# Arduino_EPROM_Reader.net
KiCad netlist of a schematic drawn in EAGLE
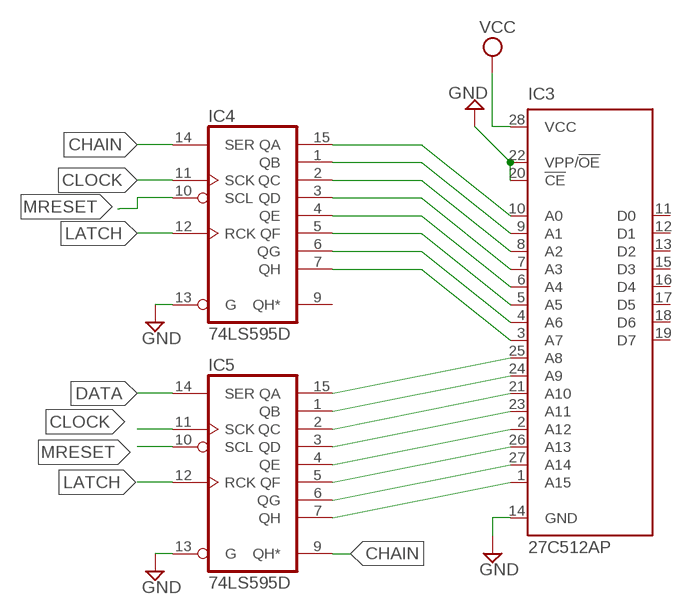
[diagram p0: schematic, sheet 1]

(export (version "E")
  (design (tool "Eeschema 10.0.6"))
  (components
    (comp (ref "IC3")
      (value "27C512AP")
      (footprint "eagle-import:DIL28-6")
      (fields (field (name "MPN") "M27C512-90B6"))
      (libsource (lib "eagle-import") (part "27512APC"))
    )
    (comp (ref "IC4")
      (value "74LS595D")
      (footprint "eagle-import:SO16")
      (libsource (lib "eagle-import") (part "74595DLS"))
    )
    (comp (ref "IC5")
      (value "74LS595D")
      (footprint "eagle-import:SO16")
      (libsource (lib "eagle-import") (part "74595DLS"))
    )
  )
  (nets
    (net (code "1") (name "CHAIN") (class "Default")
      (node (ref "IC4") (pin "14") (pinfunction "SER_14") (pintype "input"))
      (node (ref "IC5") (pin "9") (pinfunction "QH*_9") (pintype "tri_state"))
    )
    (net (code "2") (name "CLOCK") (class "Default")
      (node (ref "IC4") (pin "11") (pinfunction "SCK_11") (pintype "input"))
      (node (ref "IC5") (pin "11") (pinfunction "SCK_11") (pintype "input"))
    )
    (net (code "3") (name "DATA") (class "Default")
      (node (ref "IC5") (pin "14") (pinfunction "SER_14") (pintype "input"))
    )
    (net (code "4") (name "GND") (class "Default")
      (node (ref "IC3") (pin "14") (pinfunction "GND_14") (pintype "power_in"))
      (node (ref "IC3") (pin "20") (pinfunction "~{CE}_20") (pintype "input"))
      (node (ref "IC3") (pin "22") (pinfunction "VPP/~{OE}_22") (pintype "input"))
      (node (ref "IC4") (pin "13") (pinfunction "G_13") (pintype "input"))
      (node (ref "IC5") (pin "13") (pinfunction "G_13") (pintype "input"))
    )
    (net (code "5") (name "LATCH") (class "Default")
      (node (ref "IC4") (pin "12") (pinfunction "RCK_12") (pintype "input"))
      (node (ref "IC5") (pin "12") (pinfunction "RCK_12") (pintype "input"))
    )
    (net (code "6") (name "MRESET") (class "Default")
      (node (ref "IC4") (pin "10") (pinfunction "SCL_10") (pintype "input"))
      (node (ref "IC5") (pin "10") (pinfunction "SCL_10") (pintype "input"))
    )
    (net (code "7") (name "Net-(IC3-A0)") (class "Default")
      (node (ref "IC3") (pin "10") (pinfunction "A0_10") (pintype "input"))
      (node (ref "IC4") (pin "15") (pinfunction "QA_15") (pintype "tri_state"))
    )
    (net (code "8") (name "Net-(IC3-A1)") (class "Default")
      (node (ref "IC3") (pin "9") (pinfunction "A1_9") (pintype "input"))
      (node (ref "IC4") (pin "1") (pinfunction "QB_1") (pintype "tri_state"))
    )
    (net (code "9") (name "Net-(IC3-A2)") (class "Default")
      (node (ref "IC3") (pin "8") (pinfunction "A2_8") (pintype "input"))
      (node (ref "IC4") (pin "2") (pinfunction "QC_2") (pintype "tri_state"))
    )
    (net (code "10") (name "Net-(IC3-A3)") (class "Default")
      (node (ref "IC3") (pin "7") (pinfunction "A3_7") (pintype "input"))
      (node (ref "IC4") (pin "3") (pinfunction "QD_3") (pintype "tri_state"))
    )
    (net (code "11") (name "Net-(IC3-A4)") (class "Default")
      (node (ref "IC3") (pin "6") (pinfunction "A4_6") (pintype "input"))
      (node (ref "IC4") (pin "4") (pinfunction "QE_4") (pintype "tri_state"))
    )
    (net (code "12") (name "Net-(IC3-A5)") (class "Default")
      (node (ref "IC3") (pin "5") (pinfunction "A5_5") (pintype "input"))
      (node (ref "IC4") (pin "5") (pinfunction "QF_5") (pintype "tri_state"))
    )
    (net (code "13") (name "Net-(IC3-A6)") (class "Default")
      (node (ref "IC3") (pin "4") (pinfunction "A6_4") (pintype "input"))
      (node (ref "IC4") (pin "6") (pinfunction "QG_6") (pintype "tri_state"))
    )
    (net (code "14") (name "Net-(IC3-A7)") (class "Default")
      (node (ref "IC3") (pin "3") (pinfunction "A7_3") (pintype "input"))
      (node (ref "IC4") (pin "7") (pinfunction "QH_7") (pintype "tri_state"))
    )
    (net (code "15") (name "Net-(IC3-A8)") (class "Default")
      (node (ref "IC3") (pin "25") (pinfunction "A8_25") (pintype "input"))
      (node (ref "IC5") (pin "15") (pinfunction "QA_15") (pintype "tri_state"))
    )
    (net (code "16") (name "Net-(IC3-A9)") (class "Default")
      (node (ref "IC3") (pin "24") (pinfunction "A9_24") (pintype "input"))
      (node (ref "IC5") (pin "1") (pinfunction "QB_1") (pintype "tri_state"))
    )
    (net (code "17") (name "Net-(IC3-A10)") (class "Default")
      (node (ref "IC3") (pin "21") (pinfunction "A10_21") (pintype "input"))
      (node (ref "IC5") (pin "2") (pinfunction "QC_2") (pintype "tri_state"))
    )
    (net (code "18") (name "Net-(IC3-A11)") (class "Default")
      (node (ref "IC3") (pin "23") (pinfunction "A11_23") (pintype "input"))
      (node (ref "IC5") (pin "3") (pinfunction "QD_3") (pintype "tri_state"))
    )
    (net (code "19") (name "Net-(IC3-A12)") (class "Default")
      (node (ref "IC3") (pin "2") (pinfunction "A12_2") (pintype "input"))
      (node (ref "IC5") (pin "4") (pinfunction "QE_4") (pintype "tri_state"))
    )
    (net (code "20") (name "Net-(IC3-A13)") (class "Default")
      (node (ref "IC3") (pin "26") (pinfunction "A13_26") (pintype "input"))
      (node (ref "IC5") (pin "5") (pinfunction "QF_5") (pintype "tri_state"))
    )
    (net (code "21") (name "Net-(IC3-A14)") (class "Default")
      (node (ref "IC3") (pin "27") (pinfunction "A14_27") (pintype "input"))
      (node (ref "IC5") (pin "6") (pinfunction "QG_6") (pintype "tri_state"))
    )
    (net (code "22") (name "Net-(IC3-A15)") (class "Default")
      (node (ref "IC3") (pin "1") (pinfunction "A15_1") (pintype "input"))
      (node (ref "IC5") (pin "7") (pinfunction "QH_7") (pintype "tri_state"))
    )
    (net (code "23") (name "VCC") (class "Default")
      (node (ref "IC3") (pin "28") (pinfunction "VCC_28") (pintype "power_in"))
    )
    (net (code "24") (name "unconnected-(IC3-D0-Pad11)") (class "Default")
      (node (ref "IC3") (pin "11") (pinfunction "D0_11") (pintype "tri_state"))
    )
    (net (code "25") (name "unconnected-(IC3-D1-Pad12)") (class "Default")
      (node (ref "IC3") (pin "12") (pinfunction "D1_12") (pintype "tri_state"))
    )
    (net (code "26") (name "unconnected-(IC3-D2-Pad13)") (class "Default")
      (node (ref "IC3") (pin "13") (pinfunction "D2_13") (pintype "tri_state"))
    )
    (net (code "27") (name "unconnected-(IC3-D3-Pad15)") (class "Default")
      (node (ref "IC3") (pin "15") (pinfunction "D3_15") (pintype "tri_state"))
    )
    (net (code "28") (name "unconnected-(IC3-D4-Pad16)") (class "Default")
      (node (ref "IC3") (pin "16") (pinfunction "D4_16") (pintype "tri_state"))
    )
    (net (code "29") (name "unconnected-(IC3-D5-Pad17)") (class "Default")
      (node (ref "IC3") (pin "17") (pinfunction "D5_17") (pintype "tri_state"))
    )
    (net (code "30") (name "unconnected-(IC3-D6-Pad18)") (class "Default")
      (node (ref "IC3") (pin "18") (pinfunction "D6_18") (pintype "tri_state"))
    )
    (net (code "31") (name "unconnected-(IC3-D7-Pad19)") (class "Default")
      (node (ref "IC3") (pin "19") (pinfunction "D7_19") (pintype "tri_state"))
    )
    (net (code "32") (name "unconnected-(IC4A-QH*-Pad9)") (class "Default")
      (node (ref "IC4") (pin "9") (pinfunction "QH*_9") (pintype "tri_state"))
    )
  )
)
